# usb5.net
KiCad netlist of a schematic drawn in EAGLE
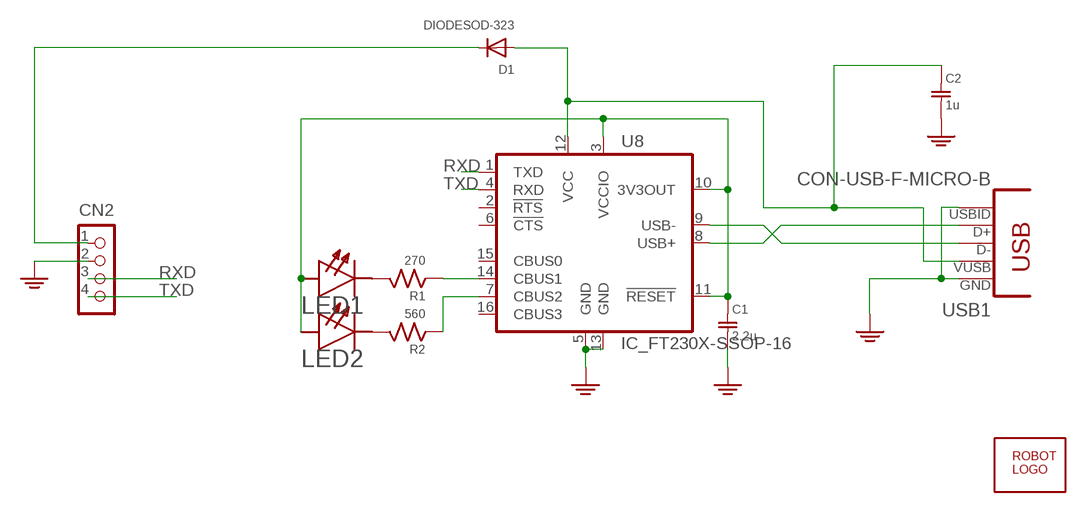
[diagram p0: schematic, sheet 1]

(export (version "E")
  (design (tool "Eeschema 10.0.6"))
  (components
    (comp (ref "C1")
      (value "2.2u")
      (footprint "eagle-import:SMD0603")
      (libsource (lib "eagle-import") (part "C0603"))
    )
    (comp (ref "C2")
      (value "1u")
      (footprint "eagle-import:SMD0603")
      (libsource (lib "eagle-import") (part "C0603"))
    )
    (comp (ref "CN2")
      (value "CON_HEADER_1X04")
      (footprint "eagle-import:M1X4")
      (libsource (lib "eagle-import") (part "CON_HEADER_1X04"))
    )
    (comp (ref "D1")
      (value "DIODESOD-323")
      (footprint "eagle-import:SOD-323")
      (libsource (lib "eagle-import") (part "DIODESOD-323"))
    )
    (comp (ref "LED1")
      (value "GREEN")
      (footprint "eagle-import:SMD0603D")
      (libsource (lib "eagle-import") (part "LED"))
    )
    (comp (ref "LED2")
      (value "ORANGE")
      (footprint "eagle-import:SMD0603D")
      (libsource (lib "eagle-import") (part "LED"))
    )
    (comp (ref "R1")
      (value "270")
      (footprint "eagle-import:SMD0603")
      (libsource (lib "eagle-import") (part "R0603"))
    )
    (comp (ref "R2")
      (value "560")
      (footprint "eagle-import:SMD0603")
      (libsource (lib "eagle-import") (part "R0603"))
    )
    (comp (ref "U$1")
      (value "ROBOTMAN-LOGO2")
      (footprint "eagle-import:ROBOTMAN-LOGO2")
      (libsource (lib "eagle-import") (part "ROBOTMAN-LOGO2"))
    )
    (comp (ref "U8")
      (value "IC_FT230X-SSOP-16")
      (footprint "eagle-import:SSOP-16-FTDI")
      (libsource (lib "eagle-import") (part "IC_FT230X-SSOP-16"))
    )
    (comp (ref "USB1")
      (value "CON-USB-F-MICRO-B")
      (footprint "eagle-import:CONN_USB_MICRO-B")
      (libsource (lib "eagle-import") (part "CON-USB-F-MICRO-B"))
    )
  )
  (nets
    (net (code "1") (name "/RXD") (class "Default")
      (node (ref "CN2") (pin "3") (pinfunction "3_3") (pintype "bidirectional"))
      (node (ref "U8") (pin "1") (pinfunction "TXD_1") (pintype "output"))
    )
    (net (code "2") (name "/TXD") (class "Default")
      (node (ref "CN2") (pin "4") (pinfunction "4_4") (pintype "bidirectional"))
      (node (ref "U8") (pin "4") (pinfunction "RXD_4") (pintype "input"))
    )
    (net (code "3") (name "Net-(C1-P$1)") (class "Default")
      (node (ref "C1") (pin "1") (pinfunction "P$1_1") (pintype "passive"))
      (node (ref "LED1") (pin "A") (pinfunction "A_A") (pintype "passive"))
      (node (ref "LED2") (pin "A") (pinfunction "A_A") (pintype "passive"))
      (node (ref "U8") (pin "10") (pinfunction "3V3OUT_10") (pintype "power_in"))
      (node (ref "U8") (pin "11") (pinfunction "~{RESET}_11") (pintype "bidirectional"))
      (node (ref "U8") (pin "3") (pinfunction "VCCIO_3") (pintype "power_in"))
    )
    (net (code "4") (name "Net-(C2-P$1)") (class "Default")
      (node (ref "C2") (pin "1") (pinfunction "P$1_1") (pintype "passive"))
      (node (ref "D1") (pin "A") (pinfunction "A_A") (pintype "passive"))
      (node (ref "U8") (pin "12") (pinfunction "VCC_12") (pintype "power_in"))
      (node (ref "USB1") (pin "P1") (pinfunction "VUSB_P1") (pintype "bidirectional"))
    )
    (net (code "5") (name "Net-(CN2-Pad1)") (class "Default")
      (node (ref "CN2") (pin "1") (pinfunction "1_1") (pintype "bidirectional"))
      (node (ref "D1") (pin "C") (pinfunction "C_C") (pintype "passive"))
    )
    (net (code "6") (name "Net-(R1-P$1)") (class "Default")
      (node (ref "R1") (pin "1") (pinfunction "P$1_1") (pintype "passive"))
      (node (ref "U8") (pin "14") (pinfunction "CBUS1_14") (pintype "bidirectional"))
    )
    (net (code "7") (name "Net-(R1-P$2)") (class "Default")
      (node (ref "LED1") (pin "C") (pinfunction "C_C") (pintype "passive"))
      (node (ref "R1") (pin "2") (pinfunction "P$2_2") (pintype "passive"))
    )
    (net (code "8") (name "Net-(R2-P$1)") (class "Default")
      (node (ref "R2") (pin "1") (pinfunction "P$1_1") (pintype "passive"))
      (node (ref "U8") (pin "7") (pinfunction "CBUS2_7") (pintype "bidirectional"))
    )
    (net (code "9") (name "Net-(R2-P$2)") (class "Default")
      (node (ref "LED2") (pin "C") (pinfunction "C_C") (pintype "passive"))
      (node (ref "R2") (pin "2") (pinfunction "P$2_2") (pintype "passive"))
    )
    (net (code "10") (name "Net-(U8-USB+)") (class "Default")
      (node (ref "U8") (pin "8") (pinfunction "USB+_8") (pintype "output"))
      (node (ref "USB1") (pin "P3") (pinfunction "D+_P3") (pintype "bidirectional"))
    )
    (net (code "11") (name "Net-(U8-USB-)") (class "Default")
      (node (ref "U8") (pin "9") (pinfunction "USB-_9") (pintype "input"))
      (node (ref "USB1") (pin "P2") (pinfunction "D-_P2") (pintype "bidirectional"))
    )
    (net (code "12") (name "PWR-GND") (class "Default")
      (node (ref "C1") (pin "2") (pinfunction "P$2_2") (pintype "passive"))
      (node (ref "C2") (pin "2") (pinfunction "P$2_2") (pintype "passive"))
      (node (ref "CN2") (pin "2") (pinfunction "2_2") (pintype "bidirectional"))
      (node (ref "U8") (pin "13") (pinfunction "GND_13") (pintype "power_in"))
      (node (ref "U8") (pin "5") (pinfunction "GND_5") (pintype "power_in"))
      (node (ref "USB1") (pin "P4") (pinfunction "USBID_P4") (pintype "bidirectional"))
      (node (ref "USB1") (pin "P5") (pinfunction "GND_P5") (pintype "bidirectional"))
    )
    (net (code "13") (name "unconnected-(U8-CBUS0-Pad15)") (class "Default")
      (node (ref "U8") (pin "15") (pinfunction "CBUS0_15") (pintype "bidirectional"))
    )
    (net (code "14") (name "unconnected-(U8-CBUS3-Pad16)") (class "Default")
      (node (ref "U8") (pin "16") (pinfunction "CBUS3_16") (pintype "bidirectional"))
    )
    (net (code "15") (name "unconnected-(U8-~{CTS}-Pad6)") (class "Default")
      (node (ref "U8") (pin "6") (pinfunction "~{CTS}_6") (pintype "bidirectional"))
    )
    (net (code "16") (name "unconnected-(U8-~{RTS}-Pad2)") (class "Default")
      (node (ref "U8") (pin "2") (pinfunction "~{RTS}_2") (pintype "bidirectional"))
    )
  )
)
